# motordriver-v5_0_opto-isolation-ctrl.net
KiCad netlist of a schematic drawn in Altium Designer
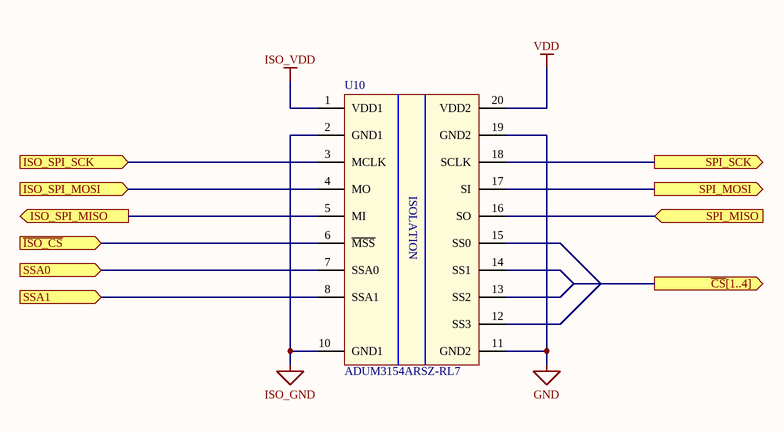
[diagram p0: motordriver-v5.0_opto-isolation-ctrl.SchDoc]

(export (version "E")
  (design (tool "Eeschema 10.0.6"))
  (components
    (comp (ref "U10")
      (value "ADUM3154ARSZ-RL7")
      (footprint "20-SSOP")
      (description "DGTL ISO 3.75KV 4CH SPI 20SSOP")
      (fields (field (name "MANUFACTURER") "Analog Devices"))
      (libsource (lib "AltiumLibraries") (part "ISO ADUM3154ARSZ-RL7"))
    )
  )
  (nets
    (net (code "5") (name "/ISO_SPI_MISO") (class "Default")
      (node (ref "U10") (pin "5") (pinfunction "MI_5") (pintype "passive"))
    )
    (net (code "6") (name "/ISO_SPI_MOSI") (class "Default")
      (node (ref "U10") (pin "4") (pinfunction "MO_4") (pintype "passive"))
    )
    (net (code "7") (name "/ISO_SPI_SCK") (class "Default")
      (node (ref "U10") (pin "3") (pinfunction "MCLK_3") (pintype "passive"))
    )
    (net (code "8") (name "/SPI_MISO") (class "Default")
      (node (ref "U10") (pin "16") (pinfunction "SO_16") (pintype "passive"))
    )
    (net (code "9") (name "/SPI_MOSI") (class "Default")
      (node (ref "U10") (pin "17") (pinfunction "SI_17") (pintype "passive"))
    )
    (net (code "10") (name "/SPI_SCK") (class "Default")
      (node (ref "U10") (pin "18") (pinfunction "SCLK_18") (pintype "passive"))
    )
    (net (code "11") (name "/SSA0") (class "Default")
      (node (ref "U10") (pin "7") (pinfunction "SSA0_7") (pintype "passive"))
    )
    (net (code "12") (name "/SSA1") (class "Default")
      (node (ref "U10") (pin "8") (pinfunction "SSA1_8") (pintype "passive"))
    )
    (net (code "14") (name "/~{ISO_CS}") (class "Default")
      (node (ref "U10") (pin "6") (pinfunction "~{MSS}_6") (pintype "passive"))
    )
    (net (code "15") (name "GND") (class "Default")
      (node (ref "U10") (pin "11") (pinfunction "GND2_11") (pintype "passive"))
      (node (ref "U10") (pin "19") (pinfunction "GND2_19") (pintype "passive"))
    )
    (net (code "16") (name "ISO_GND") (class "Default")
      (node (ref "U10") (pin "10") (pinfunction "GND1_10") (pintype "passive"))
      (node (ref "U10") (pin "2") (pinfunction "GND1_2") (pintype "passive"))
    )
    (net (code "17") (name "ISO_VDD") (class "Default")
      (node (ref "U10") (pin "1") (pinfunction "VDD1_1") (pintype "passive"))
    )
    (net (code "18") (name "VDD") (class "Default")
      (node (ref "U10") (pin "20") (pinfunction "VDD2_20") (pintype "passive"))
    )
    (net (code "19") (name "unconnected-(U10-SS0-Pad15)") (class "Default")
      (node (ref "U10") (pin "15") (pinfunction "SS0_15") (pintype "passive"))
    )
    (net (code "20") (name "unconnected-(U10-SS1-Pad14)") (class "Default")
      (node (ref "U10") (pin "14") (pinfunction "SS1_14") (pintype "passive"))
    )
    (net (code "21") (name "unconnected-(U10-SS2-Pad13)") (class "Default")
      (node (ref "U10") (pin "13") (pinfunction "SS2_13") (pintype "passive"))
    )
    (net (code "22") (name "unconnected-(U10-SS3-Pad12)") (class "Default")
      (node (ref "U10") (pin "12") (pinfunction "SS3_12") (pintype "passive"))
    )
  )
)
